# Vital_Sign_Logger_Connector.net
KiCad netlist of a schematic drawn in Altium Designer
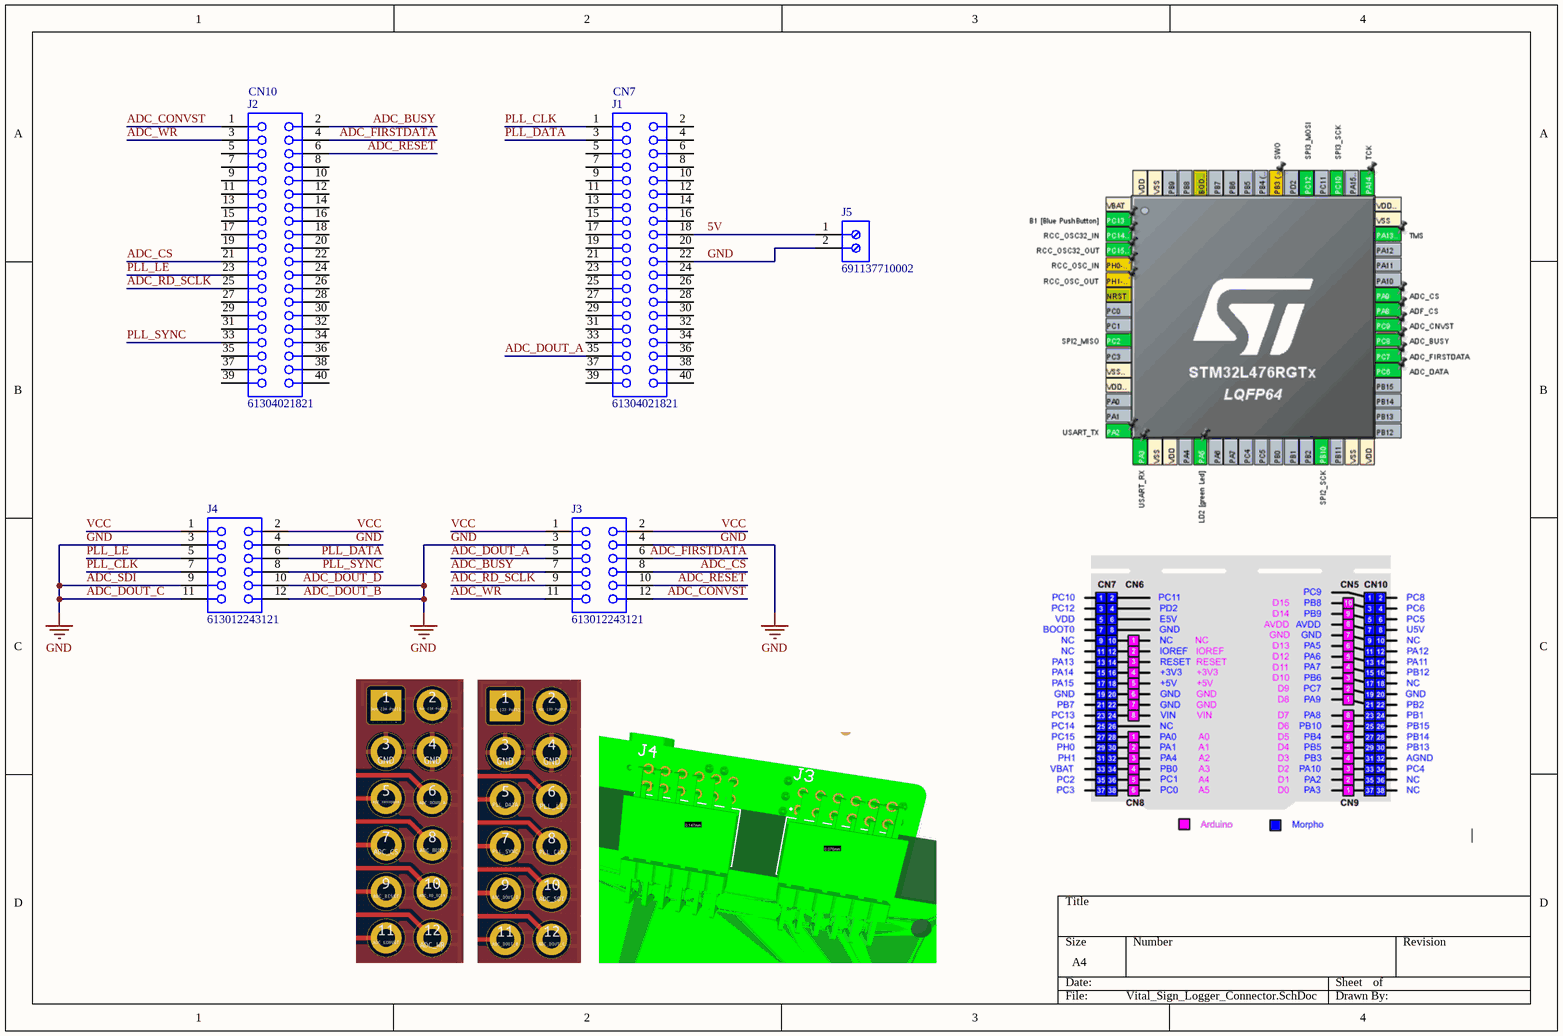
[diagram p0: Vital_Sign_Logger_Connector.SchDoc]

(export (version "E")
  (design (tool "Eeschema 10.0.6"))
  (components
    (comp (ref "J1")
      (value "61304021821")
      (footprint "61304021821")
      (libsource (lib "Altium Content Vault") (part "Header_Female_2R_40P"))
    )
    (comp (ref "J2")
      (value "61304021821")
      (footprint "61304021821")
      (libsource (lib "Altium Content Vault") (part "Header_Female_2R_40P"))
    )
    (comp (ref "J3")
      (value "613012243121")
      (footprint "613012243121")
      (libsource (lib "Altium Content Vault") (part "Header_Female_2R_12P"))
    )
    (comp (ref "J4")
      (value "613012243121")
      (footprint "613012243121")
      (libsource (lib "Altium Content Vault") (part "Header_Female_2R_12P"))
    )
    (comp (ref "J5")
      (value "691137710002")
      (footprint "691137710002")
      (libsource (lib "Altium Content Vault") (part "TBL - 1R - 02P - Screw"))
    )
  )
  (nets
    (net (code "1") (name "/5V") (class "Default")
      (node (ref "J1") (pin "18") (pinfunction "18_18") (pintype "passive"))
      (node (ref "J5") (pin "1") (pinfunction "1_1") (pintype "passive"))
    )
    (net (code "2") (name "/ADC_BUSY") (class "Default")
      (node (ref "J2") (pin "2") (pinfunction "2_2") (pintype "passive"))
      (node (ref "J3") (pin "7") (pinfunction "7_7") (pintype "passive"))
    )
    (net (code "3") (name "/ADC_CONVST") (class "Default")
      (node (ref "J2") (pin "1") (pinfunction "1_1") (pintype "passive"))
      (node (ref "J3") (pin "12") (pinfunction "12_12") (pintype "passive"))
    )
    (net (code "4") (name "/ADC_CS") (class "Default")
      (node (ref "J2") (pin "21") (pinfunction "21_21") (pintype "passive"))
      (node (ref "J3") (pin "8") (pinfunction "8_8") (pintype "passive"))
    )
    (net (code "5") (name "/ADC_DOUT_A") (class "Default")
      (node (ref "J1") (pin "35") (pinfunction "35_35") (pintype "passive"))
      (node (ref "J3") (pin "5") (pinfunction "5_5") (pintype "passive"))
    )
    (net (code "6") (name "/ADC_FIRSTDATA") (class "Default")
      (node (ref "J2") (pin "4") (pinfunction "4_4") (pintype "passive"))
      (node (ref "J3") (pin "6") (pinfunction "6_6") (pintype "passive"))
    )
    (net (code "7") (name "/ADC_RD_SCLK") (class "Default")
      (node (ref "J2") (pin "25") (pinfunction "25_25") (pintype "passive"))
      (node (ref "J3") (pin "9") (pinfunction "9_9") (pintype "passive"))
    )
    (net (code "8") (name "/ADC_RESET") (class "Default")
      (node (ref "J2") (pin "6") (pinfunction "6_6") (pintype "passive"))
      (node (ref "J3") (pin "10") (pinfunction "10_10") (pintype "passive"))
    )
    (net (code "9") (name "/ADC_WR") (class "Default")
      (node (ref "J2") (pin "3") (pinfunction "3_3") (pintype "passive"))
      (node (ref "J3") (pin "11") (pinfunction "11_11") (pintype "passive"))
    )
    (net (code "10") (name "/PLL_CLK") (class "Default")
      (node (ref "J1") (pin "1") (pinfunction "1_1") (pintype "passive"))
      (node (ref "J4") (pin "7") (pinfunction "7_7") (pintype "passive"))
    )
    (net (code "11") (name "/PLL_DATA") (class "Default")
      (node (ref "J1") (pin "3") (pinfunction "3_3") (pintype "passive"))
      (node (ref "J4") (pin "6") (pinfunction "6_6") (pintype "passive"))
    )
    (net (code "12") (name "/PLL_LE") (class "Default")
      (node (ref "J2") (pin "23") (pinfunction "23_23") (pintype "passive"))
      (node (ref "J4") (pin "5") (pinfunction "5_5") (pintype "passive"))
    )
    (net (code "13") (name "/PLL_SYNC") (class "Default")
      (node (ref "J2") (pin "33") (pinfunction "33_33") (pintype "passive"))
      (node (ref "J4") (pin "8") (pinfunction "8_8") (pintype "passive"))
    )
    (net (code "14") (name "/VCC") (class "Default")
      (node (ref "J3") (pin "1") (pinfunction "1_1") (pintype "passive"))
      (node (ref "J3") (pin "2") (pinfunction "2_2") (pintype "passive"))
      (node (ref "J4") (pin "1") (pinfunction "1_1") (pintype "passive"))
      (node (ref "J4") (pin "2") (pinfunction "2_2") (pintype "passive"))
    )
    (net (code "15") (name "GND") (class "Default")
      (node (ref "J1") (pin "22") (pinfunction "22_22") (pintype "passive"))
      (node (ref "J3") (pin "3") (pinfunction "3_3") (pintype "passive"))
      (node (ref "J3") (pin "4") (pinfunction "4_4") (pintype "passive"))
      (node (ref "J4") (pin "10") (pinfunction "10_10") (pintype "passive"))
      (node (ref "J4") (pin "11") (pinfunction "11_11") (pintype "passive"))
      (node (ref "J4") (pin "12") (pinfunction "12_12") (pintype "passive"))
      (node (ref "J4") (pin "3") (pinfunction "3_3") (pintype "passive"))
      (node (ref "J4") (pin "4") (pinfunction "4_4") (pintype "passive"))
      (node (ref "J4") (pin "9") (pinfunction "9_9") (pintype "passive"))
      (node (ref "J5") (pin "2") (pinfunction "2_2") (pintype "passive"))
    )
    (net (code "16") (name "unconnected-(J1-Pad2)") (class "Default")
      (node (ref "J1") (pin "2") (pinfunction "2_2") (pintype "passive"))
    )
    (net (code "17") (name "unconnected-(J1-Pad4)") (class "Default")
      (node (ref "J1") (pin "4") (pinfunction "4_4") (pintype "passive"))
    )
    (net (code "18") (name "unconnected-(J1-Pad5)") (class "Default")
      (node (ref "J1") (pin "5") (pinfunction "5_5") (pintype "passive"))
    )
    (net (code "19") (name "unconnected-(J1-Pad6)") (class "Default")
      (node (ref "J1") (pin "6") (pinfunction "6_6") (pintype "passive"))
    )
    (net (code "20") (name "unconnected-(J1-Pad7)") (class "Default")
      (node (ref "J1") (pin "7") (pinfunction "7_7") (pintype "passive"))
    )
    (net (code "21") (name "unconnected-(J1-Pad8)") (class "Default")
      (node (ref "J1") (pin "8") (pinfunction "8_8") (pintype "passive"))
    )
    (net (code "22") (name "unconnected-(J1-Pad9)") (class "Default")
      (node (ref "J1") (pin "9") (pinfunction "9_9") (pintype "passive"))
    )
    (net (code "23") (name "unconnected-(J1-Pad10)") (class "Default")
      (node (ref "J1") (pin "10") (pinfunction "10_10") (pintype "passive"))
    )
    (net (code "24") (name "unconnected-(J1-Pad11)") (class "Default")
      (node (ref "J1") (pin "11") (pinfunction "11_11") (pintype "passive"))
    )
    (net (code "25") (name "unconnected-(J1-Pad12)") (class "Default")
      (node (ref "J1") (pin "12") (pinfunction "12_12") (pintype "passive"))
    )
    (net (code "26") (name "unconnected-(J1-Pad13)") (class "Default")
      (node (ref "J1") (pin "13") (pinfunction "13_13") (pintype "passive"))
    )
    (net (code "27") (name "unconnected-(J1-Pad14)") (class "Default")
      (node (ref "J1") (pin "14") (pinfunction "14_14") (pintype "passive"))
    )
    (net (code "28") (name "unconnected-(J1-Pad15)") (class "Default")
      (node (ref "J1") (pin "15") (pinfunction "15_15") (pintype "passive"))
    )
    (net (code "29") (name "unconnected-(J1-Pad16)") (class "Default")
      (node (ref "J1") (pin "16") (pinfunction "16_16") (pintype "passive"))
    )
    (net (code "30") (name "unconnected-(J1-Pad17)") (class "Default")
      (node (ref "J1") (pin "17") (pinfunction "17_17") (pintype "passive"))
    )
    (net (code "31") (name "unconnected-(J1-Pad19)") (class "Default")
      (node (ref "J1") (pin "19") (pinfunction "19_19") (pintype "passive"))
    )
    (net (code "32") (name "unconnected-(J1-Pad20)") (class "Default")
      (node (ref "J1") (pin "20") (pinfunction "20_20") (pintype "passive"))
    )
    (net (code "33") (name "unconnected-(J1-Pad21)") (class "Default")
      (node (ref "J1") (pin "21") (pinfunction "21_21") (pintype "passive"))
    )
    (net (code "34") (name "unconnected-(J1-Pad23)") (class "Default")
      (node (ref "J1") (pin "23") (pinfunction "23_23") (pintype "passive"))
    )
    (net (code "35") (name "unconnected-(J1-Pad24)") (class "Default")
      (node (ref "J1") (pin "24") (pinfunction "24_24") (pintype "passive"))
    )
    (net (code "36") (name "unconnected-(J1-Pad25)") (class "Default")
      (node (ref "J1") (pin "25") (pinfunction "25_25") (pintype "passive"))
    )
    (net (code "37") (name "unconnected-(J1-Pad26)") (class "Default")
      (node (ref "J1") (pin "26") (pinfunction "26_26") (pintype "passive"))
    )
    (net (code "38") (name "unconnected-(J1-Pad27)") (class "Default")
      (node (ref "J1") (pin "27") (pinfunction "27_27") (pintype "passive"))
    )
    (net (code "39") (name "unconnected-(J1-Pad28)") (class "Default")
      (node (ref "J1") (pin "28") (pinfunction "28_28") (pintype "passive"))
    )
    (net (code "40") (name "unconnected-(J1-Pad29)") (class "Default")
      (node (ref "J1") (pin "29") (pinfunction "29_29") (pintype "passive"))
    )
    (net (code "41") (name "unconnected-(J1-Pad30)") (class "Default")
      (node (ref "J1") (pin "30") (pinfunction "30_30") (pintype "passive"))
    )
    (net (code "42") (name "unconnected-(J1-Pad31)") (class "Default")
      (node (ref "J1") (pin "31") (pinfunction "31_31") (pintype "passive"))
    )
    (net (code "43") (name "unconnected-(J1-Pad32)") (class "Default")
      (node (ref "J1") (pin "32") (pinfunction "32_32") (pintype "passive"))
    )
    (net (code "44") (name "unconnected-(J1-Pad33)") (class "Default")
      (node (ref "J1") (pin "33") (pinfunction "33_33") (pintype "passive"))
    )
    (net (code "45") (name "unconnected-(J1-Pad34)") (class "Default")
      (node (ref "J1") (pin "34") (pinfunction "34_34") (pintype "passive"))
    )
    (net (code "46") (name "unconnected-(J1-Pad36)") (class "Default")
      (node (ref "J1") (pin "36") (pinfunction "36_36") (pintype "passive"))
    )
    (net (code "47") (name "unconnected-(J1-Pad37)") (class "Default")
      (node (ref "J1") (pin "37") (pinfunction "37_37") (pintype "passive"))
    )
    (net (code "48") (name "unconnected-(J1-Pad38)") (class "Default")
      (node (ref "J1") (pin "38") (pinfunction "38_38") (pintype "passive"))
    )
    (net (code "49") (name "unconnected-(J1-Pad39)") (class "Default")
      (node (ref "J1") (pin "39") (pinfunction "39_39") (pintype "passive"))
    )
    (net (code "50") (name "unconnected-(J1-Pad40)") (class "Default")
      (node (ref "J1") (pin "40") (pinfunction "40_40") (pintype "passive"))
    )
    (net (code "51") (name "unconnected-(J2-Pad5)") (class "Default")
      (node (ref "J2") (pin "5") (pinfunction "5_5") (pintype "passive"))
    )
    (net (code "52") (name "unconnected-(J2-Pad7)") (class "Default")
      (node (ref "J2") (pin "7") (pinfunction "7_7") (pintype "passive"))
    )
    (net (code "53") (name "unconnected-(J2-Pad8)") (class "Default")
      (node (ref "J2") (pin "8") (pinfunction "8_8") (pintype "passive"))
    )
    (net (code "54") (name "unconnected-(J2-Pad9)") (class "Default")
      (node (ref "J2") (pin "9") (pinfunction "9_9") (pintype "passive"))
    )
    (net (code "55") (name "unconnected-(J2-Pad10)") (class "Default")
      (node (ref "J2") (pin "10") (pinfunction "10_10") (pintype "passive"))
    )
    (net (code "56") (name "unconnected-(J2-Pad11)") (class "Default")
      (node (ref "J2") (pin "11") (pinfunction "11_11") (pintype "passive"))
    )
    (net (code "57") (name "unconnected-(J2-Pad12)") (class "Default")
      (node (ref "J2") (pin "12") (pinfunction "12_12") (pintype "passive"))
    )
    (net (code "58") (name "unconnected-(J2-Pad13)") (class "Default")
      (node (ref "J2") (pin "13") (pinfunction "13_13") (pintype "passive"))
    )
    (net (code "59") (name "unconnected-(J2-Pad14)") (class "Default")
      (node (ref "J2") (pin "14") (pinfunction "14_14") (pintype "passive"))
    )
    (net (code "60") (name "unconnected-(J2-Pad15)") (class "Default")
      (node (ref "J2") (pin "15") (pinfunction "15_15") (pintype "passive"))
    )
    (net (code "61") (name "unconnected-(J2-Pad16)") (class "Default")
      (node (ref "J2") (pin "16") (pinfunction "16_16") (pintype "passive"))
    )
    (net (code "62") (name "unconnected-(J2-Pad17)") (class "Default")
      (node (ref "J2") (pin "17") (pinfunction "17_17") (pintype "passive"))
    )
    (net (code "63") (name "unconnected-(J2-Pad18)") (class "Default")
      (node (ref "J2") (pin "18") (pinfunction "18_18") (pintype "passive"))
    )
    (net (code "64") (name "unconnected-(J2-Pad19)") (class "Default")
      (node (ref "J2") (pin "19") (pinfunction "19_19") (pintype "passive"))
    )
    (net (code "65") (name "unconnected-(J2-Pad20)") (class "Default")
      (node (ref "J2") (pin "20") (pinfunction "20_20") (pintype "passive"))
    )
    (net (code "66") (name "unconnected-(J2-Pad22)") (class "Default")
      (node (ref "J2") (pin "22") (pinfunction "22_22") (pintype "passive"))
    )
    (net (code "67") (name "unconnected-(J2-Pad24)") (class "Default")
      (node (ref "J2") (pin "24") (pinfunction "24_24") (pintype "passive"))
    )
    (net (code "68") (name "unconnected-(J2-Pad26)") (class "Default")
      (node (ref "J2") (pin "26") (pinfunction "26_26") (pintype "passive"))
    )
    (net (code "69") (name "unconnected-(J2-Pad27)") (class "Default")
      (node (ref "J2") (pin "27") (pinfunction "27_27") (pintype "passive"))
    )
    (net (code "70") (name "unconnected-(J2-Pad28)") (class "Default")
      (node (ref "J2") (pin "28") (pinfunction "28_28") (pintype "passive"))
    )
    (net (code "71") (name "unconnected-(J2-Pad29)") (class "Default")
      (node (ref "J2") (pin "29") (pinfunction "29_29") (pintype "passive"))
    )
    (net (code "72") (name "unconnected-(J2-Pad30)") (class "Default")
      (node (ref "J2") (pin "30") (pinfunction "30_30") (pintype "passive"))
    )
    (net (code "73") (name "unconnected-(J2-Pad31)") (class "Default")
      (node (ref "J2") (pin "31") (pinfunction "31_31") (pintype "passive"))
    )
    (net (code "74") (name "unconnected-(J2-Pad32)") (class "Default")
      (node (ref "J2") (pin "32") (pinfunction "32_32") (pintype "passive"))
    )
    (net (code "75") (name "unconnected-(J2-Pad34)") (class "Default")
      (node (ref "J2") (pin "34") (pinfunction "34_34") (pintype "passive"))
    )
    (net (code "76") (name "unconnected-(J2-Pad35)") (class "Default")
      (node (ref "J2") (pin "35") (pinfunction "35_35") (pintype "passive"))
    )
    (net (code "77") (name "unconnected-(J2-Pad36)") (class "Default")
      (node (ref "J2") (pin "36") (pinfunction "36_36") (pintype "passive"))
    )
    (net (code "78") (name "unconnected-(J2-Pad37)") (class "Default")
      (node (ref "J2") (pin "37") (pinfunction "37_37") (pintype "passive"))
    )
    (net (code "79") (name "unconnected-(J2-Pad38)") (class "Default")
      (node (ref "J2") (pin "38") (pinfunction "38_38") (pintype "passive"))
    )
    (net (code "80") (name "unconnected-(J2-Pad39)") (class "Default")
      (node (ref "J2") (pin "39") (pinfunction "39_39") (pintype "passive"))
    )
    (net (code "81") (name "unconnected-(J2-Pad40)") (class "Default")
      (node (ref "J2") (pin "40") (pinfunction "40_40") (pintype "passive"))
    )
  )
)
